# TDA1308_DualHPAmp.net
KiCad netlist of a schematic drawn in EAGLE
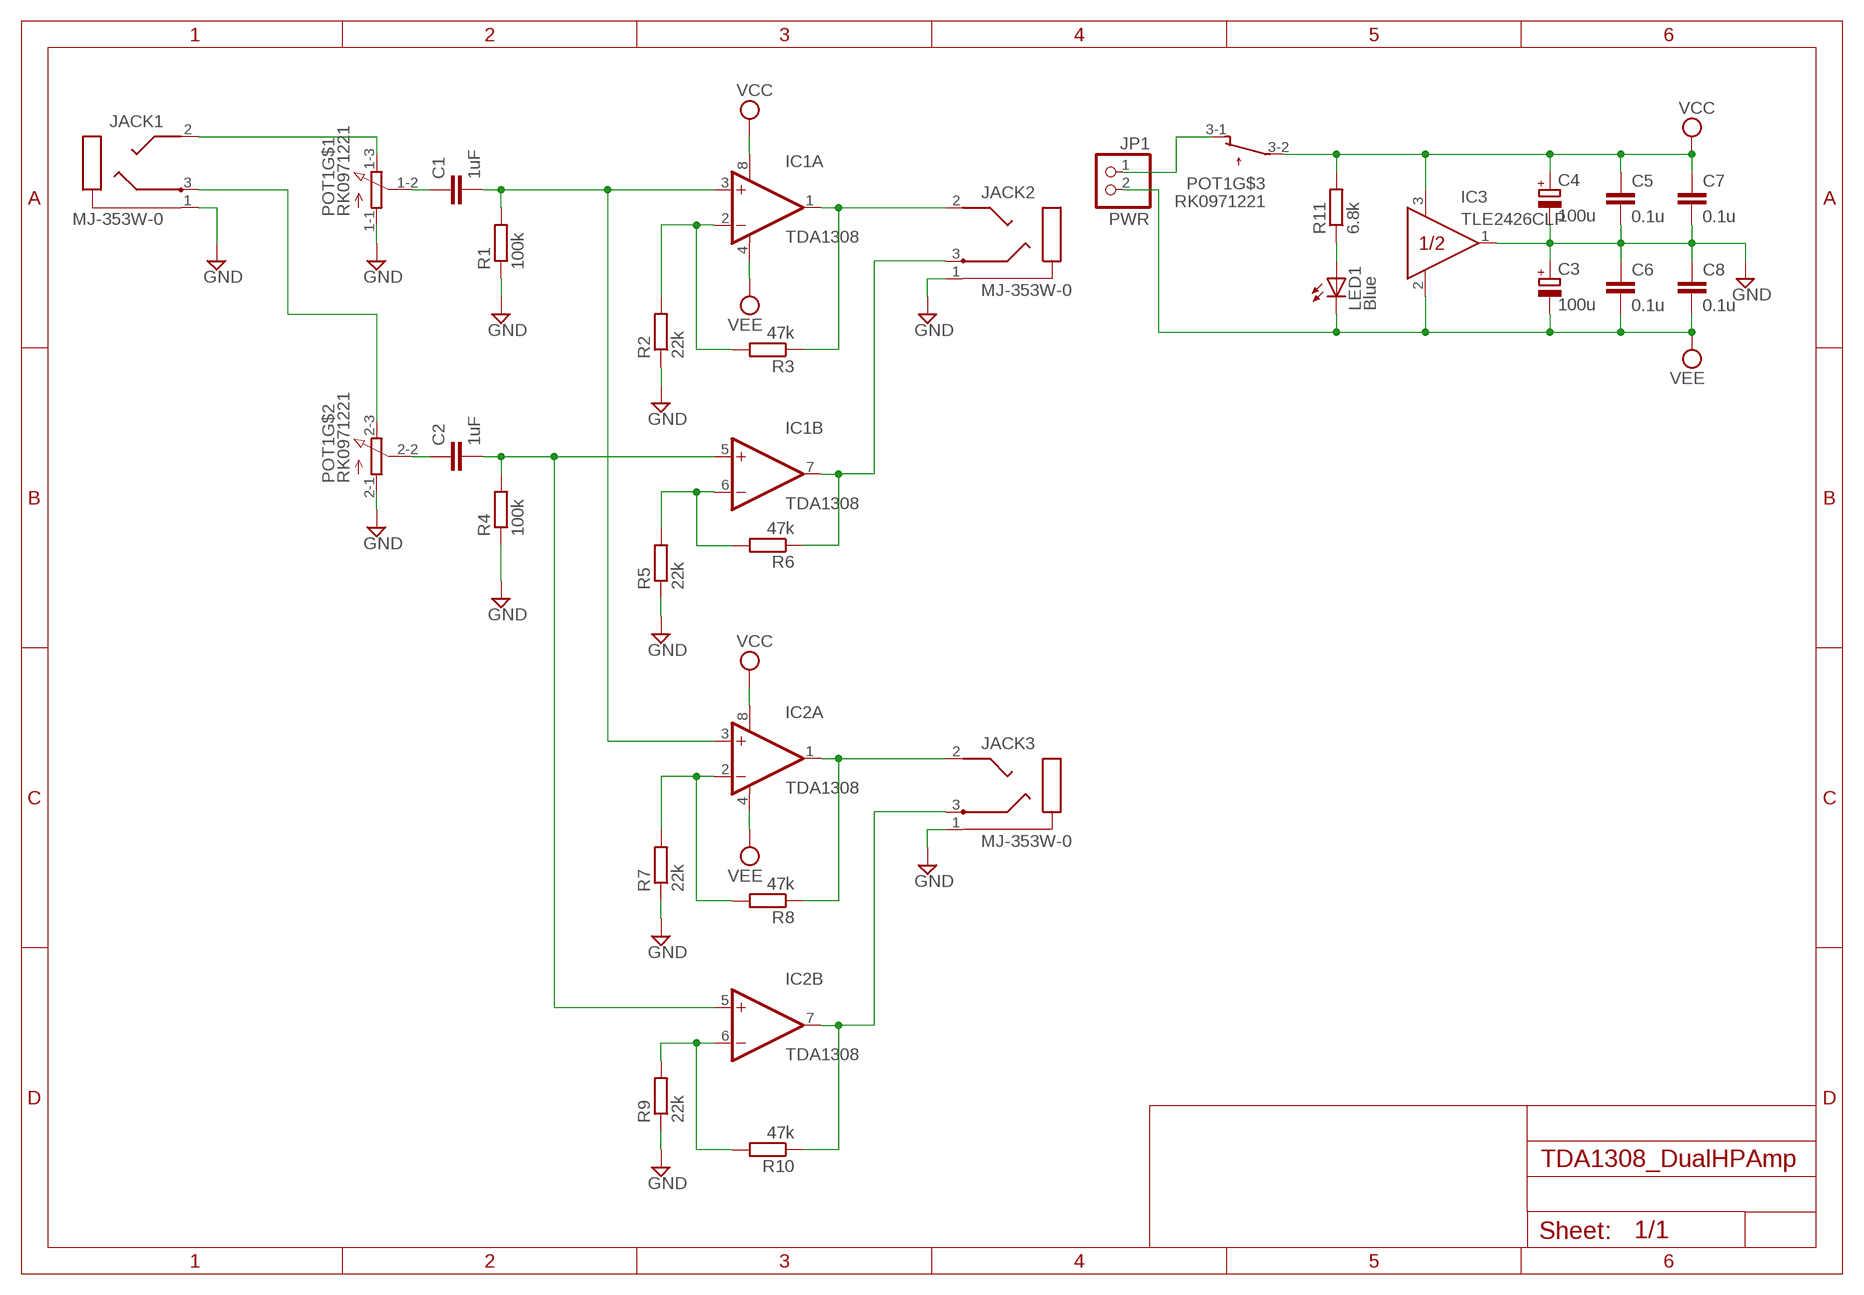
[diagram p0: schematic, sheet 1]

(export (version "E")
  (design (tool "Eeschema 10.0.6"))
  (components
    (comp (ref "C1")
      (value "1uF")
      (footprint "eagle-import:C050-050X075")
      (libsource (lib "eagle-import") (part "C-EU050-050X075"))
    )
    (comp (ref "C2")
      (value "1uF")
      (footprint "eagle-import:C050-050X075")
      (libsource (lib "eagle-import") (part "C-EU050-050X075"))
    )
    (comp (ref "C3")
      (value "100u")
      (footprint "eagle-import:E2,5-7")
      (libsource (lib "eagle-import") (part "CPOL-EUE2.5-7"))
    )
    (comp (ref "C4")
      (value "100u")
      (footprint "eagle-import:E2,5-7")
      (libsource (lib "eagle-import") (part "CPOL-EUE2.5-7"))
    )
    (comp (ref "C5")
      (value "0.1u")
      (footprint "eagle-import:C050-024X044")
      (libsource (lib "eagle-import") (part "C-EU050-024X044"))
    )
    (comp (ref "C6")
      (value "0.1u")
      (footprint "eagle-import:C025-024X044")
      (libsource (lib "eagle-import") (part "C-EU025-024X044"))
    )
    (comp (ref "C7")
      (value "0.1u")
      (footprint "eagle-import:C050-024X044")
      (libsource (lib "eagle-import") (part "C-EU050-024X044"))
    )
    (comp (ref "C8")
      (value "0.1u")
      (footprint "eagle-import:C025-024X044")
      (libsource (lib "eagle-import") (part "C-EU025-024X044"))
    )
    (comp (ref "IC1")
      (value "TDA1308")
      (footprint "eagle-import:DIL08")
      (fields (field (name "MF") "TEXAS INSTRUMENTS") (field (name "MPN") "OPA2134PA"))
      (libsource (lib "eagle-import") (part "OPA2134P"))
    )
    (comp (ref "IC2")
      (value "TDA1308")
      (footprint "eagle-import:DIL08")
      (fields (field (name "MF") "TEXAS INSTRUMENTS") (field (name "MPN") "OPA2134PA"))
      (libsource (lib "eagle-import") (part "OPA2134P"))
    )
    (comp (ref "IC3")
      (value "TLE2426CLP")
      (footprint "eagle-import:TO226AA")
      (libsource (lib "eagle-import") (part "TLE2426LPC"))
    )
    (comp (ref "JACK1")
      (value "MJ-353W-0")
      (footprint "eagle-import:MJ-3052W-0")
      (libsource (lib "eagle-import") (part "MJ-353W-0"))
    )
    (comp (ref "JACK2")
      (value "MJ-353W-0")
      (footprint "eagle-import:MJ-3052W-0")
      (libsource (lib "eagle-import") (part "MJ-353W-0"))
    )
    (comp (ref "JACK3")
      (value "MJ-353W-0")
      (footprint "eagle-import:MJ-3052W-0")
      (libsource (lib "eagle-import") (part "MJ-353W-0"))
    )
    (comp (ref "JP1")
      (value "PWR")
      (footprint "eagle-import:1X02")
      (libsource (lib "eagle-import") (part "PINHD-1X2"))
    )
    (comp (ref "LED1")
      (value "Blue")
      (footprint "eagle-import:LED3MM")
      (libsource (lib "eagle-import") (part "LED3MM"))
    )
    (comp (ref "POT1")
      (value "RK0971221")
      (footprint "eagle-import:RK0971221")
      (libsource (lib "eagle-import") (part "RK0971221"))
    )
    (comp (ref "R1")
      (value "100k")
      (footprint "eagle-import:0207_2V")
      (libsource (lib "eagle-import") (part "R-EU_0207/2V"))
    )
    (comp (ref "R2")
      (value "22k")
      (footprint "eagle-import:0207_2V")
      (libsource (lib "eagle-import") (part "R-EU_0207/2V"))
    )
    (comp (ref "R3")
      (value "47k")
      (footprint "eagle-import:0207_2V")
      (libsource (lib "eagle-import") (part "R-EU_0207/2V"))
    )
    (comp (ref "R4")
      (value "100k")
      (footprint "eagle-import:0207_2V")
      (libsource (lib "eagle-import") (part "R-EU_0207/2V"))
    )
    (comp (ref "R5")
      (value "22k")
      (footprint "eagle-import:0207_7")
      (libsource (lib "eagle-import") (part "R-EU_0207/7"))
    )
    (comp (ref "R6")
      (value "47k")
      (footprint "eagle-import:0207_2V")
      (libsource (lib "eagle-import") (part "R-EU_0207/2V"))
    )
    (comp (ref "R7")
      (value "22k")
      (footprint "eagle-import:0207_2V")
      (libsource (lib "eagle-import") (part "R-EU_0207/2V"))
    )
    (comp (ref "R8")
      (value "47k")
      (footprint "eagle-import:0207_2V")
      (libsource (lib "eagle-import") (part "R-EU_0207/2V"))
    )
    (comp (ref "R9")
      (value "22k")
      (footprint "eagle-import:0207_2V")
      (libsource (lib "eagle-import") (part "R-EU_0207/2V"))
    )
    (comp (ref "R10")
      (value "47k")
      (footprint "eagle-import:0207_2V")
      (libsource (lib "eagle-import") (part "R-EU_0207/2V"))
    )
    (comp (ref "R11")
      (value "6.8k")
      (footprint "eagle-import:0207_7")
      (libsource (lib "eagle-import") (part "R-EU_0207/7"))
    )
  )
  (nets
    (net (code "1") (name "GND") (class "Default")
      (node (ref "C3") (pin "+") (pinfunction "+_+") (pintype "passive"))
      (node (ref "C4") (pin "-") (pinfunction "-_-") (pintype "passive"))
      (node (ref "C5") (pin "2") (pinfunction "2_2") (pintype "passive"))
      (node (ref "C6") (pin "1") (pinfunction "1_1") (pintype "passive"))
      (node (ref "C7") (pin "2") (pinfunction "2_2") (pintype "passive"))
      (node (ref "C8") (pin "1") (pinfunction "1_1") (pintype "passive"))
      (node (ref "IC3") (pin "1") (pinfunction "OUT_1") (pintype "passive"))
      (node (ref "JACK1") (pin "1") (pinfunction "1_1") (pintype "passive"))
      (node (ref "JACK2") (pin "1") (pinfunction "1_1") (pintype "passive"))
      (node (ref "JACK3") (pin "1") (pinfunction "1_1") (pintype "passive"))
      (node (ref "POT1") (pin "1-1") (pinfunction "A_1-1") (pintype "passive"))
      (node (ref "POT1") (pin "2-1") (pinfunction "A_2-1") (pintype "passive"))
      (node (ref "R1") (pin "1") (pinfunction "1_1") (pintype "passive"))
      (node (ref "R2") (pin "1") (pinfunction "1_1") (pintype "passive"))
      (node (ref "R4") (pin "1") (pinfunction "1_1") (pintype "passive"))
      (node (ref "R5") (pin "1") (pinfunction "1_1") (pintype "passive"))
      (node (ref "R7") (pin "1") (pinfunction "1_1") (pintype "passive"))
      (node (ref "R9") (pin "1") (pinfunction "1_1") (pintype "passive"))
    )
    (net (code "2") (name "Net-(IC1A-+IN)") (class "Default")
      (node (ref "C1") (pin "2") (pinfunction "2_2") (pintype "passive"))
      (node (ref "IC1") (pin "3") (pinfunction "+IN_3") (pintype "input"))
      (node (ref "IC2") (pin "3") (pinfunction "+IN_3") (pintype "input"))
      (node (ref "R1") (pin "2") (pinfunction "2_2") (pintype "passive"))
    )
    (net (code "3") (name "Net-(IC1A--IN)") (class "Default")
      (node (ref "IC1") (pin "2") (pinfunction "-IN_2") (pintype "input"))
      (node (ref "R2") (pin "2") (pinfunction "2_2") (pintype "passive"))
      (node (ref "R3") (pin "2") (pinfunction "2_2") (pintype "passive"))
    )
    (net (code "4") (name "Net-(IC1A-OUT)") (class "Default")
      (node (ref "IC1") (pin "1") (pinfunction "OUT_1") (pintype "output"))
      (node (ref "JACK2") (pin "2") (pinfunction "2_2") (pintype "passive"))
      (node (ref "R3") (pin "1") (pinfunction "1_1") (pintype "passive"))
    )
    (net (code "5") (name "Net-(IC1B-+IN)") (class "Default")
      (node (ref "C2") (pin "2") (pinfunction "2_2") (pintype "passive"))
      (node (ref "IC1") (pin "5") (pinfunction "+IN_5") (pintype "input"))
      (node (ref "IC2") (pin "5") (pinfunction "+IN_5") (pintype "input"))
      (node (ref "R4") (pin "2") (pinfunction "2_2") (pintype "passive"))
    )
    (net (code "6") (name "Net-(IC1B--IN)") (class "Default")
      (node (ref "IC1") (pin "6") (pinfunction "-IN_6") (pintype "input"))
      (node (ref "R5") (pin "2") (pinfunction "2_2") (pintype "passive"))
      (node (ref "R6") (pin "2") (pinfunction "2_2") (pintype "passive"))
    )
    (net (code "7") (name "Net-(IC1B-OUT)") (class "Default")
      (node (ref "IC1") (pin "7") (pinfunction "OUT_7") (pintype "output"))
      (node (ref "JACK2") (pin "3") (pinfunction "3_3") (pintype "passive"))
      (node (ref "R6") (pin "1") (pinfunction "1_1") (pintype "passive"))
    )
    (net (code "8") (name "Net-(IC2A--IN)") (class "Default")
      (node (ref "IC2") (pin "2") (pinfunction "-IN_2") (pintype "input"))
      (node (ref "R7") (pin "2") (pinfunction "2_2") (pintype "passive"))
      (node (ref "R8") (pin "2") (pinfunction "2_2") (pintype "passive"))
    )
    (net (code "9") (name "Net-(IC2A-OUT)") (class "Default")
      (node (ref "IC2") (pin "1") (pinfunction "OUT_1") (pintype "output"))
      (node (ref "JACK3") (pin "2") (pinfunction "2_2") (pintype "passive"))
      (node (ref "R8") (pin "1") (pinfunction "1_1") (pintype "passive"))
    )
    (net (code "10") (name "Net-(IC2B--IN)") (class "Default")
      (node (ref "IC2") (pin "6") (pinfunction "-IN_6") (pintype "input"))
      (node (ref "R10") (pin "2") (pinfunction "2_2") (pintype "passive"))
      (node (ref "R9") (pin "2") (pinfunction "2_2") (pintype "passive"))
    )
    (net (code "11") (name "Net-(IC2B-OUT)") (class "Default")
      (node (ref "IC2") (pin "7") (pinfunction "OUT_7") (pintype "output"))
      (node (ref "JACK3") (pin "3") (pinfunction "3_3") (pintype "passive"))
      (node (ref "R10") (pin "1") (pinfunction "1_1") (pintype "passive"))
    )
    (net (code "12") (name "Net-(LED1-PadA)") (class "Default")
      (node (ref "LED1") (pin "A") (pinfunction "A_A") (pintype "passive"))
      (node (ref "R11") (pin "1") (pinfunction "1_1") (pintype "passive"))
    )
    (net (code "13") (name "Net-(POT1A-E)") (class "Default")
      (node (ref "JACK1") (pin "2") (pinfunction "2_2") (pintype "passive"))
      (node (ref "POT1") (pin "1-3") (pinfunction "E_1-3") (pintype "passive"))
    )
    (net (code "14") (name "Net-(POT1A-S)") (class "Default")
      (node (ref "C1") (pin "1") (pinfunction "1_1") (pintype "passive"))
      (node (ref "POT1") (pin "1-2") (pinfunction "S_1-2") (pintype "passive"))
    )
    (net (code "15") (name "Net-(POT1B-E)") (class "Default")
      (node (ref "JACK1") (pin "3") (pinfunction "3_3") (pintype "passive"))
      (node (ref "POT1") (pin "2-3") (pinfunction "E_2-3") (pintype "passive"))
    )
    (net (code "16") (name "Net-(POT1B-S)") (class "Default")
      (node (ref "C2") (pin "1") (pinfunction "1_1") (pintype "passive"))
      (node (ref "POT1") (pin "2-2") (pinfunction "S_2-2") (pintype "passive"))
    )
    (net (code "17") (name "Net-(POT1C-O)") (class "Default")
      (node (ref "JP1") (pin "1") (pinfunction "1_1") (pintype "passive"))
      (node (ref "POT1") (pin "3-1") (pinfunction "O_3-1") (pintype "passive"))
    )
    (net (code "18") (name "VCC") (class "Default")
      (node (ref "C4") (pin "+") (pinfunction "+_+") (pintype "passive"))
      (node (ref "C5") (pin "1") (pinfunction "1_1") (pintype "passive"))
      (node (ref "C7") (pin "1") (pinfunction "1_1") (pintype "passive"))
      (node (ref "IC1") (pin "8") (pinfunction "V+_8") (pintype "power_in"))
      (node (ref "IC2") (pin "8") (pinfunction "V+_8") (pintype "power_in"))
      (node (ref "IC3") (pin "3") (pinfunction "IN_3") (pintype "passive"))
      (node (ref "POT1") (pin "3-2") (pinfunction "P_3-2") (pintype "passive"))
      (node (ref "R11") (pin "2") (pinfunction "2_2") (pintype "passive"))
    )
    (net (code "19") (name "VEE") (class "Default")
      (node (ref "C3") (pin "-") (pinfunction "-_-") (pintype "passive"))
      (node (ref "C6") (pin "2") (pinfunction "2_2") (pintype "passive"))
      (node (ref "C8") (pin "2") (pinfunction "2_2") (pintype "passive"))
      (node (ref "IC1") (pin "4") (pinfunction "V-_4") (pintype "power_in"))
      (node (ref "IC2") (pin "4") (pinfunction "V-_4") (pintype "power_in"))
      (node (ref "IC3") (pin "2") (pinfunction "COM_2") (pintype "passive"))
      (node (ref "JP1") (pin "2") (pinfunction "2_2") (pintype "passive"))
      (node (ref "LED1") (pin "K") (pinfunction "C_K") (pintype "passive"))
    )
  )
)
